# board.net
KiCad netlist of a schematic drawn in EAGLE
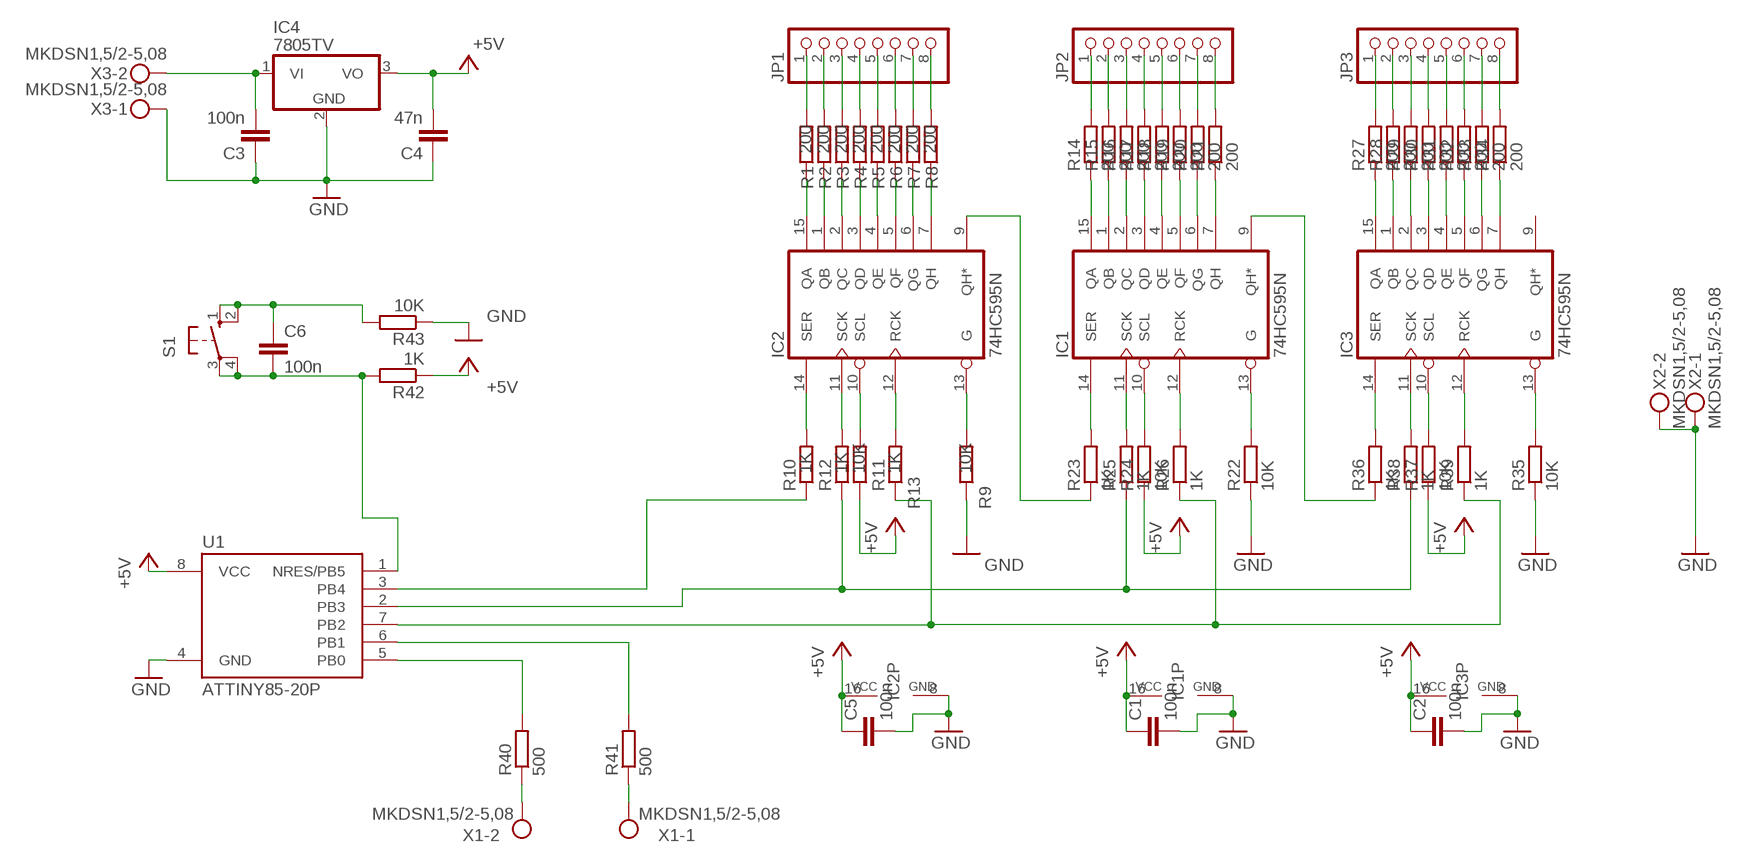
[diagram p0: schematic, sheet 1]

(export (version "E")
  (design (tool "Eeschema 10.0.6"))
  (components
    (comp (ref "C1")
      (value "100n")
      (footprint "eagle-import:C5B3")
      (libsource (lib "eagle-import") (part "C5/3"))
    )
    (comp (ref "C2")
      (value "100n")
      (footprint "eagle-import:C5B3")
      (libsource (lib "eagle-import") (part "C5/3"))
    )
    (comp (ref "C3")
      (value "100n")
      (footprint "eagle-import:C5B3")
      (libsource (lib "eagle-import") (part "C5/3"))
    )
    (comp (ref "C4")
      (value "47n")
      (footprint "eagle-import:C5B3")
      (libsource (lib "eagle-import") (part "C5/3"))
    )
    (comp (ref "C5")
      (value "100n")
      (footprint "eagle-import:C5B3")
      (libsource (lib "eagle-import") (part "C5/3"))
    )
    (comp (ref "C6")
      (value "100n")
      (footprint "eagle-import:C5B3")
      (libsource (lib "eagle-import") (part "C5/3"))
    )
    (comp (ref "IC1")
      (value "74HC595N")
      (footprint "eagle-import:DIL16")
      (libsource (lib "eagle-import") (part "74595NHC"))
    )
    (comp (ref "IC2")
      (value "74HC595N")
      (footprint "eagle-import:DIL16")
      (libsource (lib "eagle-import") (part "74595NHC"))
    )
    (comp (ref "IC3")
      (value "74HC595N")
      (footprint "eagle-import:DIL16")
      (libsource (lib "eagle-import") (part "74595NHC"))
    )
    (comp (ref "IC4")
      (value "7805TV")
      (footprint "eagle-import:TO220V")
      (libsource (lib "eagle-import") (part "78TV05"))
    )
    (comp (ref "JP1")
      (value "PINHD-1X8")
      (footprint "eagle-import:1X08")
      (libsource (lib "eagle-import") (part "PINHD-1X8"))
    )
    (comp (ref "JP2")
      (value "PINHD-1X8")
      (footprint "eagle-import:1X08")
      (libsource (lib "eagle-import") (part "PINHD-1X8"))
    )
    (comp (ref "JP3")
      (value "PINHD-1X8")
      (footprint "eagle-import:1X08")
      (libsource (lib "eagle-import") (part "PINHD-1X8"))
    )
    (comp (ref "R1")
      (value "200")
      (footprint "eagle-import:0207_10")
      (libsource (lib "eagle-import") (part "R-EU_0207/10"))
    )
    (comp (ref "R2")
      (value "200")
      (footprint "eagle-import:0207_10")
      (libsource (lib "eagle-import") (part "R-EU_0207/10"))
    )
    (comp (ref "R3")
      (value "200")
      (footprint "eagle-import:0207_10")
      (libsource (lib "eagle-import") (part "R-EU_0207/10"))
    )
    (comp (ref "R4")
      (value "200")
      (footprint "eagle-import:0207_10")
      (libsource (lib "eagle-import") (part "R-EU_0207/10"))
    )
    (comp (ref "R5")
      (value "200")
      (footprint "eagle-import:0207_10")
      (libsource (lib "eagle-import") (part "R-EU_0207/10"))
    )
    (comp (ref "R6")
      (value "200")
      (footprint "eagle-import:0207_10")
      (libsource (lib "eagle-import") (part "R-EU_0207/10"))
    )
    (comp (ref "R7")
      (value "200")
      (footprint "eagle-import:0207_10")
      (libsource (lib "eagle-import") (part "R-EU_0207/10"))
    )
    (comp (ref "R8")
      (value "200")
      (footprint "eagle-import:0207_10")
      (libsource (lib "eagle-import") (part "R-EU_0207/10"))
    )
    (comp (ref "R9")
      (value "10K")
      (footprint "eagle-import:0207_10")
      (libsource (lib "eagle-import") (part "R-EU_0207/10"))
    )
    (comp (ref "R10")
      (value "1K")
      (footprint "eagle-import:0207_10")
      (libsource (lib "eagle-import") (part "R-EU_0207/10"))
    )
    (comp (ref "R11")
      (value "10K")
      (footprint "eagle-import:0207_10")
      (libsource (lib "eagle-import") (part "R-EU_0207/10"))
    )
    (comp (ref "R12")
      (value "1K")
      (footprint "eagle-import:0207_10")
      (libsource (lib "eagle-import") (part "R-EU_0207/10"))
    )
    (comp (ref "R13")
      (value "1K")
      (footprint "eagle-import:0207_10")
      (libsource (lib "eagle-import") (part "R-EU_0207/10"))
    )
    (comp (ref "R14")
      (value "200")
      (footprint "eagle-import:0207_10")
      (libsource (lib "eagle-import") (part "R-EU_0207/10"))
    )
    (comp (ref "R15")
      (value "200")
      (footprint "eagle-import:0207_10")
      (libsource (lib "eagle-import") (part "R-EU_0207/10"))
    )
    (comp (ref "R16")
      (value "200")
      (footprint "eagle-import:0207_10")
      (libsource (lib "eagle-import") (part "R-EU_0207/10"))
    )
    (comp (ref "R17")
      (value "200")
      (footprint "eagle-import:0207_10")
      (libsource (lib "eagle-import") (part "R-EU_0207/10"))
    )
    (comp (ref "R18")
      (value "200")
      (footprint "eagle-import:0207_10")
      (libsource (lib "eagle-import") (part "R-EU_0207/10"))
    )
    (comp (ref "R19")
      (value "200")
      (footprint "eagle-import:0207_10")
      (libsource (lib "eagle-import") (part "R-EU_0207/10"))
    )
    (comp (ref "R20")
      (value "200")
      (footprint "eagle-import:0207_10")
      (libsource (lib "eagle-import") (part "R-EU_0207/10"))
    )
    (comp (ref "R21")
      (value "200")
      (footprint "eagle-import:0207_10")
      (libsource (lib "eagle-import") (part "R-EU_0207/10"))
    )
    (comp (ref "R22")
      (value "10K")
      (footprint "eagle-import:0207_10")
      (libsource (lib "eagle-import") (part "R-EU_0207/10"))
    )
    (comp (ref "R23")
      (value "1K")
      (footprint "eagle-import:0207_10")
      (libsource (lib "eagle-import") (part "R-EU_0207/10"))
    )
    (comp (ref "R24")
      (value "10K")
      (footprint "eagle-import:0207_10")
      (libsource (lib "eagle-import") (part "R-EU_0207/10"))
    )
    (comp (ref "R25")
      (value "1K")
      (footprint "eagle-import:0207_10")
      (libsource (lib "eagle-import") (part "R-EU_0207/10"))
    )
    (comp (ref "R26")
      (value "1K")
      (footprint "eagle-import:0207_10")
      (libsource (lib "eagle-import") (part "R-EU_0207/10"))
    )
    (comp (ref "R27")
      (value "200")
      (footprint "eagle-import:0207_10")
      (libsource (lib "eagle-import") (part "R-EU_0207/10"))
    )
    (comp (ref "R28")
      (value "200")
      (footprint "eagle-import:0207_10")
      (libsource (lib "eagle-import") (part "R-EU_0207/10"))
    )
    (comp (ref "R29")
      (value "200")
      (footprint "eagle-import:0207_10")
      (libsource (lib "eagle-import") (part "R-EU_0207/10"))
    )
    (comp (ref "R30")
      (value "200")
      (footprint "eagle-import:0207_10")
      (libsource (lib "eagle-import") (part "R-EU_0207/10"))
    )
    (comp (ref "R31")
      (value "200")
      (footprint "eagle-import:0207_10")
      (libsource (lib "eagle-import") (part "R-EU_0207/10"))
    )
    (comp (ref "R32")
      (value "200")
      (footprint "eagle-import:0207_10")
      (libsource (lib "eagle-import") (part "R-EU_0207/10"))
    )
    (comp (ref "R33")
      (value "200")
      (footprint "eagle-import:0207_10")
      (libsource (lib "eagle-import") (part "R-EU_0207/10"))
    )
    (comp (ref "R34")
      (value "200")
      (footprint "eagle-import:0207_10")
      (libsource (lib "eagle-import") (part "R-EU_0207/10"))
    )
    (comp (ref "R35")
      (value "10K")
      (footprint "eagle-import:0207_10")
      (libsource (lib "eagle-import") (part "R-EU_0207/10"))
    )
    (comp (ref "R36")
      (value "1K")
      (footprint "eagle-import:0207_10")
      (libsource (lib "eagle-import") (part "R-EU_0207/10"))
    )
    (comp (ref "R37")
      (value "10K")
      (footprint "eagle-import:0207_10")
      (libsource (lib "eagle-import") (part "R-EU_0207/10"))
    )
    (comp (ref "R38")
      (value "1K")
      (footprint "eagle-import:0207_10")
      (libsource (lib "eagle-import") (part "R-EU_0207/10"))
    )
    (comp (ref "R39")
      (value "1K")
      (footprint "eagle-import:0207_10")
      (libsource (lib "eagle-import") (part "R-EU_0207/10"))
    )
    (comp (ref "R40")
      (value "500")
      (footprint "eagle-import:0207_10")
      (libsource (lib "eagle-import") (part "R-EU_0207/10"))
    )
    (comp (ref "R41")
      (value "500")
      (footprint "eagle-import:0207_10")
      (libsource (lib "eagle-import") (part "R-EU_0207/10"))
    )
    (comp (ref "R42")
      (value "1K")
      (footprint "eagle-import:0207_10")
      (libsource (lib "eagle-import") (part "R-EU_0207/10"))
    )
    (comp (ref "R43")
      (value "10K")
      (footprint "eagle-import:0207_10")
      (libsource (lib "eagle-import") (part "R-EU_0207/10"))
    )
    (comp (ref "S1")
      (value "10-XX")
      (footprint "eagle-import:B3F-10XX")
      (fields (field (name "MPN") "B3F-1000"))
      (libsource (lib "eagle-import") (part "10-XX"))
    )
    (comp (ref "U1")
      (value "ATTINY85-20P")
      (footprint "eagle-import:PDIP08_300MIL")
      (libsource (lib "eagle-import") (part "ATTINY85P-20"))
    )
    (comp (ref "X1")
      (value "MKDSN1,5/2-5,08")
      (footprint "eagle-import:MKDSN1,5_2-5,08")
      (libsource (lib "eagle-import") (part "MKDSN1,5/2-5,08"))
    )
    (comp (ref "X2")
      (value "MKDSN1,5/2-5,08")
      (footprint "eagle-import:MKDSN1,5_2-5,08")
      (libsource (lib "eagle-import") (part "MKDSN1,5/2-5,08"))
    )
    (comp (ref "X3")
      (value "MKDSN1,5/2-5,08")
      (footprint "eagle-import:MKDSN1,5_2-5,08")
      (libsource (lib "eagle-import") (part "MKDSN1,5/2-5,08"))
    )
  )
  (nets
    (net (code "1") (name "+5V") (class "Default")
      (node (ref "C1") (pin "1") (pinfunction "1_1") (pintype "passive"))
      (node (ref "C2") (pin "1") (pinfunction "1_1") (pintype "passive"))
      (node (ref "C4") (pin "2") (pinfunction "2_2") (pintype "passive"))
      (node (ref "C5") (pin "1") (pinfunction "1_1") (pintype "passive"))
      (node (ref "IC1") (pin "16") (pinfunction "VCC_16") (pintype "power_in"))
      (node (ref "IC2") (pin "16") (pinfunction "VCC_16") (pintype "power_in"))
      (node (ref "IC3") (pin "16") (pinfunction "VCC_16") (pintype "power_in"))
      (node (ref "IC4") (pin "3") (pinfunction "VO_3") (pintype "passive"))
      (node (ref "R11") (pin "1") (pinfunction "1_1") (pintype "passive"))
      (node (ref "R24") (pin "1") (pinfunction "1_1") (pintype "passive"))
      (node (ref "R37") (pin "1") (pinfunction "1_1") (pintype "passive"))
      (node (ref "R42") (pin "1") (pinfunction "1_1") (pintype "passive"))
      (node (ref "U1") (pin "8") (pinfunction "VCC_8") (pintype "power_in"))
    )
    (net (code "2") (name "GND") (class "Default")
      (node (ref "C1") (pin "2") (pinfunction "2_2") (pintype "passive"))
      (node (ref "C2") (pin "2") (pinfunction "2_2") (pintype "passive"))
      (node (ref "C3") (pin "1") (pinfunction "1_1") (pintype "passive"))
      (node (ref "C4") (pin "1") (pinfunction "1_1") (pintype "passive"))
      (node (ref "C5") (pin "2") (pinfunction "2_2") (pintype "passive"))
      (node (ref "IC1") (pin "8") (pinfunction "GND_8") (pintype "power_in"))
      (node (ref "IC2") (pin "8") (pinfunction "GND_8") (pintype "power_in"))
      (node (ref "IC3") (pin "8") (pinfunction "GND_8") (pintype "power_in"))
      (node (ref "IC4") (pin "2") (pinfunction "GND_2") (pintype "passive"))
      (node (ref "R22") (pin "1") (pinfunction "1_1") (pintype "passive"))
      (node (ref "R35") (pin "1") (pinfunction "1_1") (pintype "passive"))
      (node (ref "R43") (pin "1") (pinfunction "1_1") (pintype "passive"))
      (node (ref "R9") (pin "1") (pinfunction "1_1") (pintype "passive"))
      (node (ref "U1") (pin "4") (pinfunction "GND_4") (pintype "power_in"))
      (node (ref "X2") (pin "1") (pinfunction "KL_1") (pintype "passive"))
      (node (ref "X2") (pin "2") (pinfunction "KL_2") (pintype "passive"))
      (node (ref "X3") (pin "1") (pinfunction "KL_1") (pintype "passive"))
    )
    (net (code "3") (name "Net-(IC1A-G)") (class "Default")
      (node (ref "IC1") (pin "13") (pinfunction "G_13") (pintype "input"))
      (node (ref "R22") (pin "2") (pinfunction "2_2") (pintype "passive"))
    )
    (net (code "4") (name "Net-(IC1A-QA)") (class "Default")
      (node (ref "IC1") (pin "15") (pinfunction "QA_15") (pintype "tri_state"))
      (node (ref "R14") (pin "1") (pinfunction "1_1") (pintype "passive"))
    )
    (net (code "5") (name "Net-(IC1A-QB)") (class "Default")
      (node (ref "IC1") (pin "1") (pinfunction "QB_1") (pintype "tri_state"))
      (node (ref "R15") (pin "1") (pinfunction "1_1") (pintype "passive"))
    )
    (net (code "6") (name "Net-(IC1A-QC)") (class "Default")
      (node (ref "IC1") (pin "2") (pinfunction "QC_2") (pintype "tri_state"))
      (node (ref "R16") (pin "1") (pinfunction "1_1") (pintype "passive"))
    )
    (net (code "7") (name "Net-(IC1A-QD)") (class "Default")
      (node (ref "IC1") (pin "3") (pinfunction "QD_3") (pintype "tri_state"))
      (node (ref "R17") (pin "1") (pinfunction "1_1") (pintype "passive"))
    )
    (net (code "8") (name "Net-(IC1A-QE)") (class "Default")
      (node (ref "IC1") (pin "4") (pinfunction "QE_4") (pintype "tri_state"))
      (node (ref "R18") (pin "1") (pinfunction "1_1") (pintype "passive"))
    )
    (net (code "9") (name "Net-(IC1A-QF)") (class "Default")
      (node (ref "IC1") (pin "5") (pinfunction "QF_5") (pintype "tri_state"))
      (node (ref "R19") (pin "1") (pinfunction "1_1") (pintype "passive"))
    )
    (net (code "10") (name "Net-(IC1A-QG)") (class "Default")
      (node (ref "IC1") (pin "6") (pinfunction "QG_6") (pintype "tri_state"))
      (node (ref "R20") (pin "1") (pinfunction "1_1") (pintype "passive"))
    )
    (net (code "11") (name "Net-(IC1A-QH)") (class "Default")
      (node (ref "IC1") (pin "7") (pinfunction "QH_7") (pintype "tri_state"))
      (node (ref "R21") (pin "1") (pinfunction "1_1") (pintype "passive"))
    )
    (net (code "12") (name "Net-(IC1A-QH*)") (class "Default")
      (node (ref "IC1") (pin "9") (pinfunction "QH*_9") (pintype "tri_state"))
      (node (ref "R36") (pin "1") (pinfunction "1_1") (pintype "passive"))
    )
    (net (code "13") (name "Net-(IC1A-RCK)") (class "Default")
      (node (ref "IC1") (pin "12") (pinfunction "RCK_12") (pintype "input"))
      (node (ref "R26") (pin "2") (pinfunction "2_2") (pintype "passive"))
    )
    (net (code "14") (name "Net-(IC1A-SCK)") (class "Default")
      (node (ref "IC1") (pin "11") (pinfunction "SCK_11") (pintype "input"))
      (node (ref "R25") (pin "2") (pinfunction "2_2") (pintype "passive"))
    )
    (net (code "15") (name "Net-(IC1A-SCL)") (class "Default")
      (node (ref "IC1") (pin "10") (pinfunction "SCL_10") (pintype "input"))
      (node (ref "R24") (pin "2") (pinfunction "2_2") (pintype "passive"))
    )
    (net (code "16") (name "Net-(IC1A-SER)") (class "Default")
      (node (ref "IC1") (pin "14") (pinfunction "SER_14") (pintype "input"))
      (node (ref "R23") (pin "2") (pinfunction "2_2") (pintype "passive"))
    )
    (net (code "17") (name "Net-(IC2A-G)") (class "Default")
      (node (ref "IC2") (pin "13") (pinfunction "G_13") (pintype "input"))
      (node (ref "R9") (pin "2") (pinfunction "2_2") (pintype "passive"))
    )
    (net (code "18") (name "Net-(IC2A-QA)") (class "Default")
      (node (ref "IC2") (pin "15") (pinfunction "QA_15") (pintype "tri_state"))
      (node (ref "R1") (pin "1") (pinfunction "1_1") (pintype "passive"))
    )
    (net (code "19") (name "Net-(IC2A-QB)") (class "Default")
      (node (ref "IC2") (pin "1") (pinfunction "QB_1") (pintype "tri_state"))
      (node (ref "R2") (pin "1") (pinfunction "1_1") (pintype "passive"))
    )
    (net (code "20") (name "Net-(IC2A-QC)") (class "Default")
      (node (ref "IC2") (pin "2") (pinfunction "QC_2") (pintype "tri_state"))
      (node (ref "R3") (pin "1") (pinfunction "1_1") (pintype "passive"))
    )
    (net (code "21") (name "Net-(IC2A-QD)") (class "Default")
      (node (ref "IC2") (pin "3") (pinfunction "QD_3") (pintype "tri_state"))
      (node (ref "R4") (pin "1") (pinfunction "1_1") (pintype "passive"))
    )
    (net (code "22") (name "Net-(IC2A-QE)") (class "Default")
      (node (ref "IC2") (pin "4") (pinfunction "QE_4") (pintype "tri_state"))
      (node (ref "R5") (pin "1") (pinfunction "1_1") (pintype "passive"))
    )
    (net (code "23") (name "Net-(IC2A-QF)") (class "Default")
      (node (ref "IC2") (pin "5") (pinfunction "QF_5") (pintype "tri_state"))
      (node (ref "R6") (pin "1") (pinfunction "1_1") (pintype "passive"))
    )
    (net (code "24") (name "Net-(IC2A-QG)") (class "Default")
      (node (ref "IC2") (pin "6") (pinfunction "QG_6") (pintype "tri_state"))
      (node (ref "R7") (pin "1") (pinfunction "1_1") (pintype "passive"))
    )
    (net (code "25") (name "Net-(IC2A-QH)") (class "Default")
      (node (ref "IC2") (pin "7") (pinfunction "QH_7") (pintype "tri_state"))
      (node (ref "R8") (pin "1") (pinfunction "1_1") (pintype "passive"))
    )
    (net (code "26") (name "Net-(IC2A-QH*)") (class "Default")
      (node (ref "IC2") (pin "9") (pinfunction "QH*_9") (pintype "tri_state"))
      (node (ref "R23") (pin "1") (pinfunction "1_1") (pintype "passive"))
    )
    (net (code "27") (name "Net-(IC2A-RCK)") (class "Default")
      (node (ref "IC2") (pin "12") (pinfunction "RCK_12") (pintype "input"))
      (node (ref "R13") (pin "2") (pinfunction "2_2") (pintype "passive"))
    )
    (net (code "28") (name "Net-(IC2A-SCK)") (class "Default")
      (node (ref "IC2") (pin "11") (pinfunction "SCK_11") (pintype "input"))
      (node (ref "R12") (pin "2") (pinfunction "2_2") (pintype "passive"))
    )
    (net (code "29") (name "Net-(IC2A-SCL)") (class "Default")
      (node (ref "IC2") (pin "10") (pinfunction "SCL_10") (pintype "input"))
      (node (ref "R11") (pin "2") (pinfunction "2_2") (pintype "passive"))
    )
    (net (code "30") (name "Net-(IC2A-SER)") (class "Default")
      (node (ref "IC2") (pin "14") (pinfunction "SER_14") (pintype "input"))
      (node (ref "R10") (pin "2") (pinfunction "2_2") (pintype "passive"))
    )
    (net (code "31") (name "Net-(IC3A-G)") (class "Default")
      (node (ref "IC3") (pin "13") (pinfunction "G_13") (pintype "input"))
      (node (ref "R35") (pin "2") (pinfunction "2_2") (pintype "passive"))
    )
    (net (code "32") (name "Net-(IC3A-QA)") (class "Default")
      (node (ref "IC3") (pin "15") (pinfunction "QA_15") (pintype "tri_state"))
      (node (ref "R27") (pin "1") (pinfunction "1_1") (pintype "passive"))
    )
    (net (code "33") (name "Net-(IC3A-QB)") (class "Default")
      (node (ref "IC3") (pin "1") (pinfunction "QB_1") (pintype "tri_state"))
      (node (ref "R28") (pin "1") (pinfunction "1_1") (pintype "passive"))
    )
    (net (code "34") (name "Net-(IC3A-QC)") (class "Default")
      (node (ref "IC3") (pin "2") (pinfunction "QC_2") (pintype "tri_state"))
      (node (ref "R29") (pin "1") (pinfunction "1_1") (pintype "passive"))
    )
    (net (code "35") (name "Net-(IC3A-QD)") (class "Default")
      (node (ref "IC3") (pin "3") (pinfunction "QD_3") (pintype "tri_state"))
      (node (ref "R30") (pin "1") (pinfunction "1_1") (pintype "passive"))
    )
    (net (code "36") (name "Net-(IC3A-QE)") (class "Default")
      (node (ref "IC3") (pin "4") (pinfunction "QE_4") (pintype "tri_state"))
      (node (ref "R31") (pin "1") (pinfunction "1_1") (pintype "passive"))
    )
    (net (code "37") (name "Net-(IC3A-QF)") (class "Default")
      (node (ref "IC3") (pin "5") (pinfunction "QF_5") (pintype "tri_state"))
      (node (ref "R32") (pin "1") (pinfunction "1_1") (pintype "passive"))
    )
    (net (code "38") (name "Net-(IC3A-QG)") (class "Default")
      (node (ref "IC3") (pin "6") (pinfunction "QG_6") (pintype "tri_state"))
      (node (ref "R33") (pin "1") (pinfunction "1_1") (pintype "passive"))
    )
    (net (code "39") (name "Net-(IC3A-QH)") (class "Default")
      (node (ref "IC3") (pin "7") (pinfunction "QH_7") (pintype "tri_state"))
      (node (ref "R34") (pin "1") (pinfunction "1_1") (pintype "passive"))
    )
    (net (code "40") (name "Net-(IC3A-RCK)") (class "Default")
      (node (ref "IC3") (pin "12") (pinfunction "RCK_12") (pintype "input"))
      (node (ref "R39") (pin "2") (pinfunction "2_2") (pintype "passive"))
    )
    (net (code "41") (name "Net-(IC3A-SCK)") (class "Default")
      (node (ref "IC3") (pin "11") (pinfunction "SCK_11") (pintype "input"))
      (node (ref "R38") (pin "2") (pinfunction "2_2") (pintype "passive"))
    )
    (net (code "42") (name "Net-(IC3A-SCL)") (class "Default")
      (node (ref "IC3") (pin "10") (pinfunction "SCL_10") (pintype "input"))
      (node (ref "R37") (pin "2") (pinfunction "2_2") (pintype "passive"))
    )
    (net (code "43") (name "Net-(IC3A-SER)") (class "Default")
      (node (ref "IC3") (pin "14") (pinfunction "SER_14") (pintype "input"))
      (node (ref "R36") (pin "2") (pinfunction "2_2") (pintype "passive"))
    )
    (net (code "44") (name "Net-(IC4-VI)") (class "Default")
      (node (ref "C3") (pin "2") (pinfunction "2_2") (pintype "passive"))
      (node (ref "IC4") (pin "1") (pinfunction "VI_1") (pintype "input"))
      (node (ref "X3") (pin "2") (pinfunction "KL_2") (pintype "passive"))
    )
    (net (code "45") (name "Net-(JP1-Pad1)") (class "Default")
      (node (ref "JP1") (pin "1") (pinfunction "1_1") (pintype "passive"))
      (node (ref "R1") (pin "2") (pinfunction "2_2") (pintype "passive"))
    )
    (net (code "46") (name "Net-(JP1-Pad2)") (class "Default")
      (node (ref "JP1") (pin "2") (pinfunction "2_2") (pintype "passive"))
      (node (ref "R2") (pin "2") (pinfunction "2_2") (pintype "passive"))
    )
    (net (code "47") (name "Net-(JP1-Pad3)") (class "Default")
      (node (ref "JP1") (pin "3") (pinfunction "3_3") (pintype "passive"))
      (node (ref "R3") (pin "2") (pinfunction "2_2") (pintype "passive"))
    )
    (net (code "48") (name "Net-(JP1-Pad4)") (class "Default")
      (node (ref "JP1") (pin "4") (pinfunction "4_4") (pintype "passive"))
      (node (ref "R4") (pin "2") (pinfunction "2_2") (pintype "passive"))
    )
    (net (code "49") (name "Net-(JP1-Pad5)") (class "Default")
      (node (ref "JP1") (pin "5") (pinfunction "5_5") (pintype "passive"))
      (node (ref "R5") (pin "2") (pinfunction "2_2") (pintype "passive"))
    )
    (net (code "50") (name "Net-(JP1-Pad6)") (class "Default")
      (node (ref "JP1") (pin "6") (pinfunction "6_6") (pintype "passive"))
      (node (ref "R6") (pin "2") (pinfunction "2_2") (pintype "passive"))
    )
    (net (code "51") (name "Net-(JP1-Pad7)") (class "Default")
      (node (ref "JP1") (pin "7") (pinfunction "7_7") (pintype "passive"))
      (node (ref "R7") (pin "2") (pinfunction "2_2") (pintype "passive"))
    )
    (net (code "52") (name "Net-(JP1-Pad8)") (class "Default")
      (node (ref "JP1") (pin "8") (pinfunction "8_8") (pintype "passive"))
      (node (ref "R8") (pin "2") (pinfunction "2_2") (pintype "passive"))
    )
    (net (code "53") (name "Net-(JP2-Pad1)") (class "Default")
      (node (ref "JP2") (pin "1") (pinfunction "1_1") (pintype "passive"))
      (node (ref "R14") (pin "2") (pinfunction "2_2") (pintype "passive"))
    )
    (net (code "54") (name "Net-(JP2-Pad2)") (class "Default")
      (node (ref "JP2") (pin "2") (pinfunction "2_2") (pintype "passive"))
      (node (ref "R15") (pin "2") (pinfunction "2_2") (pintype "passive"))
    )
    (net (code "55") (name "Net-(JP2-Pad3)") (class "Default")
      (node (ref "JP2") (pin "3") (pinfunction "3_3") (pintype "passive"))
      (node (ref "R16") (pin "2") (pinfunction "2_2") (pintype "passive"))
    )
    (net (code "56") (name "Net-(JP2-Pad4)") (class "Default")
      (node (ref "JP2") (pin "4") (pinfunction "4_4") (pintype "passive"))
      (node (ref "R17") (pin "2") (pinfunction "2_2") (pintype "passive"))
    )
    (net (code "57") (name "Net-(JP2-Pad5)") (class "Default")
      (node (ref "JP2") (pin "5") (pinfunction "5_5") (pintype "passive"))
      (node (ref "R18") (pin "2") (pinfunction "2_2") (pintype "passive"))
    )
    (net (code "58") (name "Net-(JP2-Pad6)") (class "Default")
      (node (ref "JP2") (pin "6") (pinfunction "6_6") (pintype "passive"))
      (node (ref "R19") (pin "2") (pinfunction "2_2") (pintype "passive"))
    )
    (net (code "59") (name "Net-(JP2-Pad7)") (class "Default")
      (node (ref "JP2") (pin "7") (pinfunction "7_7") (pintype "passive"))
      (node (ref "R20") (pin "2") (pinfunction "2_2") (pintype "passive"))
    )
    (net (code "60") (name "Net-(JP2-Pad8)") (class "Default")
      (node (ref "JP2") (pin "8") (pinfunction "8_8") (pintype "passive"))
      (node (ref "R21") (pin "2") (pinfunction "2_2") (pintype "passive"))
    )
    (net (code "61") (name "Net-(JP3-Pad1)") (class "Default")
      (node (ref "JP3") (pin "1") (pinfunction "1_1") (pintype "passive"))
      (node (ref "R27") (pin "2") (pinfunction "2_2") (pintype "passive"))
    )
    (net (code "62") (name "Net-(JP3-Pad2)") (class "Default")
      (node (ref "JP3") (pin "2") (pinfunction "2_2") (pintype "passive"))
      (node (ref "R28") (pin "2") (pinfunction "2_2") (pintype "passive"))
    )
    (net (code "63") (name "Net-(JP3-Pad3)") (class "Default")
      (node (ref "JP3") (pin "3") (pinfunction "3_3") (pintype "passive"))
      (node (ref "R29") (pin "2") (pinfunction "2_2") (pintype "passive"))
    )
    (net (code "64") (name "Net-(JP3-Pad4)") (class "Default")
      (node (ref "JP3") (pin "4") (pinfunction "4_4") (pintype "passive"))
      (node (ref "R30") (pin "2") (pinfunction "2_2") (pintype "passive"))
    )
    (net (code "65") (name "Net-(JP3-Pad5)") (class "Default")
      (node (ref "JP3") (pin "5") (pinfunction "5_5") (pintype "passive"))
      (node (ref "R31") (pin "2") (pinfunction "2_2") (pintype "passive"))
    )
    (net (code "66") (name "Net-(JP3-Pad6)") (class "Default")
      (node (ref "JP3") (pin "6") (pinfunction "6_6") (pintype "passive"))
      (node (ref "R32") (pin "2") (pinfunction "2_2") (pintype "passive"))
    )
    (net (code "67") (name "Net-(JP3-Pad7)") (class "Default")
      (node (ref "JP3") (pin "7") (pinfunction "7_7") (pintype "passive"))
      (node (ref "R33") (pin "2") (pinfunction "2_2") (pintype "passive"))
    )
    (net (code "68") (name "Net-(JP3-Pad8)") (class "Default")
      (node (ref "JP3") (pin "8") (pinfunction "8_8") (pintype "passive"))
      (node (ref "R34") (pin "2") (pinfunction "2_2") (pintype "passive"))
    )
    (net (code "69") (name "Net-(S1-P)") (class "Default")
      (node (ref "C6") (pin "2") (pinfunction "2_2") (pintype "passive"))
      (node (ref "R42") (pin "2") (pinfunction "2_2") (pintype "passive"))
      (node (ref "S1") (pin "3") (pinfunction "P_3") (pintype "passive"))
      (node (ref "S1") (pin "4") (pinfunction "P1_4") (pintype "passive"))
      (node (ref "U1") (pin "1") (pinfunction "NRES/PB5_1") (pintype "bidirectional"))
    )
    (net (code "70") (name "Net-(S1-S)") (class "Default")
      (node (ref "C6") (pin "1") (pinfunction "1_1") (pintype "passive"))
      (node (ref "R43") (pin "2") (pinfunction "2_2") (pintype "passive"))
      (node (ref "S1") (pin "1") (pinfunction "S_1") (pintype "passive"))
      (node (ref "S1") (pin "2") (pinfunction "S1_2") (pintype "passive"))
    )
    (net (code "71") (name "Net-(U1-PB0)") (class "Default")
      (node (ref "R40") (pin "2") (pinfunction "2_2") (pintype "passive"))
      (node (ref "U1") (pin "5") (pinfunction "PB0_5") (pintype "bidirectional"))
    )
    (net (code "72") (name "Net-(U1-PB1)") (class "Default")
      (node (ref "R41") (pin "2") (pinfunction "2_2") (pintype "passive"))
      (node (ref "U1") (pin "6") (pinfunction "PB1_6") (pintype "bidirectional"))
    )
    (net (code "73") (name "Net-(U1-PB2)") (class "Default")
      (node (ref "R13") (pin "1") (pinfunction "1_1") (pintype "passive"))
      (node (ref "R26") (pin "1") (pinfunction "1_1") (pintype "passive"))
      (node (ref "R39") (pin "1") (pinfunction "1_1") (pintype "passive"))
      (node (ref "U1") (pin "7") (pinfunction "PB2_7") (pintype "bidirectional"))
    )
    (net (code "74") (name "Net-(U1-PB3)") (class "Default")
      (node (ref "R12") (pin "1") (pinfunction "1_1") (pintype "passive"))
      (node (ref "R25") (pin "1") (pinfunction "1_1") (pintype "passive"))
      (node (ref "R38") (pin "1") (pinfunction "1_1") (pintype "passive"))
      (node (ref "U1") (pin "2") (pinfunction "PB3_2") (pintype "bidirectional"))
    )
    (net (code "75") (name "Net-(U1-PB4)") (class "Default")
      (node (ref "R10") (pin "1") (pinfunction "1_1") (pintype "passive"))
      (node (ref "U1") (pin "3") (pinfunction "PB4_3") (pintype "bidirectional"))
    )
    (net (code "76") (name "Net-(X1A-KL)") (class "Default")
      (node (ref "R41") (pin "1") (pinfunction "1_1") (pintype "passive"))
      (node (ref "X1") (pin "1") (pinfunction "KL_1") (pintype "passive"))
    )
    (net (code "77") (name "Net-(X1B-KL)") (class "Default")
      (node (ref "R40") (pin "1") (pinfunction "1_1") (pintype "passive"))
      (node (ref "X1") (pin "2") (pinfunction "KL_2") (pintype "passive"))
    )
    (net (code "78") (name "unconnected-(IC3A-QH*-Pad9)") (class "Default")
      (node (ref "IC3") (pin "9") (pinfunction "QH*_9") (pintype "tri_state"))
    )
  )
)
